# FabDisPendant.net
KiCad netlist of a schematic drawn in EAGLE
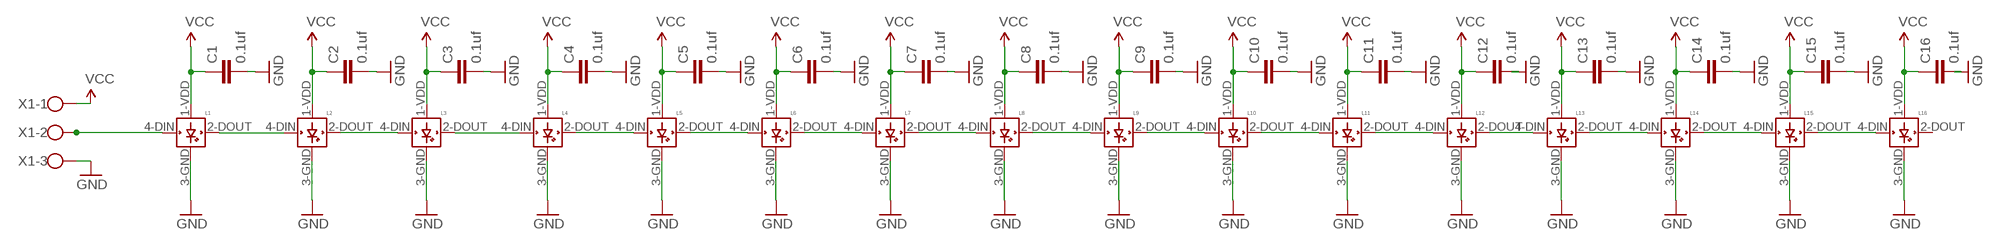
[diagram p0: schematic, sheet 1]

(export (version "E")
  (design (tool "Eeschema 10.0.6"))
  (components
    (comp (ref "C1")
      (value "0.1uf")
      (footprint "eagle-import:0603-CAP")
      (libsource (lib "eagle-import") (part "CAP0603-CAP"))
    )
    (comp (ref "C2")
      (value "0.1uf")
      (footprint "eagle-import:0603-CAP")
      (libsource (lib "eagle-import") (part "CAP0603-CAP"))
    )
    (comp (ref "C3")
      (value "0.1uf")
      (footprint "eagle-import:0603-CAP")
      (libsource (lib "eagle-import") (part "CAP0603-CAP"))
    )
    (comp (ref "C4")
      (value "0.1uf")
      (footprint "eagle-import:0603-CAP")
      (libsource (lib "eagle-import") (part "CAP0603-CAP"))
    )
    (comp (ref "C5")
      (value "0.1uf")
      (footprint "eagle-import:0603-CAP")
      (libsource (lib "eagle-import") (part "CAP0603-CAP"))
    )
    (comp (ref "C6")
      (value "0.1uf")
      (footprint "eagle-import:0603-CAP")
      (libsource (lib "eagle-import") (part "CAP0603-CAP"))
    )
    (comp (ref "C7")
      (value "0.1uf")
      (footprint "eagle-import:0603-CAP")
      (libsource (lib "eagle-import") (part "CAP0603-CAP"))
    )
    (comp (ref "C8")
      (value "0.1uf")
      (footprint "eagle-import:0603-CAP")
      (libsource (lib "eagle-import") (part "CAP0603-CAP"))
    )
    (comp (ref "C9")
      (value "0.1uf")
      (footprint "eagle-import:0603-CAP")
      (libsource (lib "eagle-import") (part "CAP0603-CAP"))
    )
    (comp (ref "C10")
      (value "0.1uf")
      (footprint "eagle-import:0603-CAP")
      (libsource (lib "eagle-import") (part "CAP0603-CAP"))
    )
    (comp (ref "C11")
      (value "0.1uf")
      (footprint "eagle-import:0603-CAP")
      (libsource (lib "eagle-import") (part "CAP0603-CAP"))
    )
    (comp (ref "C12")
      (value "0.1uf")
      (footprint "eagle-import:0603-CAP")
      (libsource (lib "eagle-import") (part "CAP0603-CAP"))
    )
    (comp (ref "C13")
      (value "0.1uf")
      (footprint "eagle-import:0603-CAP")
      (libsource (lib "eagle-import") (part "CAP0603-CAP"))
    )
    (comp (ref "C14")
      (value "0.1uf")
      (footprint "eagle-import:0603-CAP")
      (libsource (lib "eagle-import") (part "CAP0603-CAP"))
    )
    (comp (ref "C15")
      (value "0.1uf")
      (footprint "eagle-import:0603-CAP")
      (libsource (lib "eagle-import") (part "CAP0603-CAP"))
    )
    (comp (ref "C16")
      (value "0.1uf")
      (footprint "eagle-import:0603-CAP")
      (libsource (lib "eagle-import") (part "CAP0603-CAP"))
    )
    (comp (ref "L1")
      (value "WS2812B")
      (footprint "eagle-import:WS2812B")
      (libsource (lib "eagle-import") (part "WS2812B"))
    )
    (comp (ref "L2")
      (value "WS2812B")
      (footprint "eagle-import:WS2812B")
      (libsource (lib "eagle-import") (part "WS2812B"))
    )
    (comp (ref "L3")
      (value "WS2812B")
      (footprint "eagle-import:WS2812B")
      (libsource (lib "eagle-import") (part "WS2812B"))
    )
    (comp (ref "L4")
      (value "WS2812B")
      (footprint "eagle-import:WS2812B")
      (libsource (lib "eagle-import") (part "WS2812B"))
    )
    (comp (ref "L5")
      (value "WS2812B")
      (footprint "eagle-import:WS2812B")
      (libsource (lib "eagle-import") (part "WS2812B"))
    )
    (comp (ref "L6")
      (value "WS2812B")
      (footprint "eagle-import:WS2812B")
      (libsource (lib "eagle-import") (part "WS2812B"))
    )
    (comp (ref "L7")
      (value "WS2812B")
      (footprint "eagle-import:WS2812B")
      (libsource (lib "eagle-import") (part "WS2812B"))
    )
    (comp (ref "L8")
      (value "WS2812B")
      (footprint "eagle-import:WS2812B")
      (libsource (lib "eagle-import") (part "WS2812B"))
    )
    (comp (ref "L9")
      (value "WS2812B")
      (footprint "eagle-import:WS2812B")
      (libsource (lib "eagle-import") (part "WS2812B"))
    )
    (comp (ref "L10")
      (value "WS2812B")
      (footprint "eagle-import:WS2812B")
      (libsource (lib "eagle-import") (part "WS2812B"))
    )
    (comp (ref "L11")
      (value "WS2812B")
      (footprint "eagle-import:WS2812B")
      (libsource (lib "eagle-import") (part "WS2812B"))
    )
    (comp (ref "L12")
      (value "WS2812B")
      (footprint "eagle-import:WS2812B")
      (libsource (lib "eagle-import") (part "WS2812B"))
    )
    (comp (ref "L13")
      (value "WS2812B")
      (footprint "eagle-import:WS2812B")
      (libsource (lib "eagle-import") (part "WS2812B"))
    )
    (comp (ref "L14")
      (value "WS2812B")
      (footprint "eagle-import:WS2812B")
      (libsource (lib "eagle-import") (part "WS2812B"))
    )
    (comp (ref "L15")
      (value "WS2812B")
      (footprint "eagle-import:WS2812B")
      (libsource (lib "eagle-import") (part "WS2812B"))
    )
    (comp (ref "L16")
      (value "WS2812B")
      (footprint "eagle-import:WS2812B")
      (libsource (lib "eagle-import") (part "WS2812B"))
    )
    (comp (ref "X1")
      (value "W237-103")
      (footprint "eagle-import:W237-103")
      (fields (field (name "MPN") "237-103"))
      (libsource (lib "eagle-import") (part "W237-103"))
    )
  )
  (nets
    (net (code "1") (name "GND") (class "Default")
      (node (ref "C1") (pin "2") (pinfunction "2_2") (pintype "passive"))
      (node (ref "C10") (pin "2") (pinfunction "2_2") (pintype "passive"))
      (node (ref "C11") (pin "2") (pinfunction "2_2") (pintype "passive"))
      (node (ref "C12") (pin "2") (pinfunction "2_2") (pintype "passive"))
      (node (ref "C13") (pin "2") (pinfunction "2_2") (pintype "passive"))
      (node (ref "C14") (pin "2") (pinfunction "2_2") (pintype "passive"))
      (node (ref "C15") (pin "2") (pinfunction "2_2") (pintype "passive"))
      (node (ref "C16") (pin "2") (pinfunction "2_2") (pintype "passive"))
      (node (ref "C2") (pin "2") (pinfunction "2_2") (pintype "passive"))
      (node (ref "C3") (pin "2") (pinfunction "2_2") (pintype "passive"))
      (node (ref "C4") (pin "2") (pinfunction "2_2") (pintype "passive"))
      (node (ref "C5") (pin "2") (pinfunction "2_2") (pintype "passive"))
      (node (ref "C6") (pin "2") (pinfunction "2_2") (pintype "passive"))
      (node (ref "C7") (pin "2") (pinfunction "2_2") (pintype "passive"))
      (node (ref "C8") (pin "2") (pinfunction "2_2") (pintype "passive"))
      (node (ref "C9") (pin "2") (pinfunction "2_2") (pintype "passive"))
      (node (ref "L1") (pin "3-GND") (pinfunction "GND_3-GND") (pintype "bidirectional"))
      (node (ref "L10") (pin "3-GND") (pinfunction "GND_3-GND") (pintype "bidirectional"))
      (node (ref "L11") (pin "3-GND") (pinfunction "GND_3-GND") (pintype "bidirectional"))
      (node (ref "L12") (pin "3-GND") (pinfunction "GND_3-GND") (pintype "bidirectional"))
      (node (ref "L13") (pin "3-GND") (pinfunction "GND_3-GND") (pintype "bidirectional"))
      (node (ref "L14") (pin "3-GND") (pinfunction "GND_3-GND") (pintype "bidirectional"))
      (node (ref "L15") (pin "3-GND") (pinfunction "GND_3-GND") (pintype "bidirectional"))
      (node (ref "L16") (pin "3-GND") (pinfunction "GND_3-GND") (pintype "bidirectional"))
      (node (ref "L2") (pin "3-GND") (pinfunction "GND_3-GND") (pintype "bidirectional"))
      (node (ref "L3") (pin "3-GND") (pinfunction "GND_3-GND") (pintype "bidirectional"))
      (node (ref "L4") (pin "3-GND") (pinfunction "GND_3-GND") (pintype "bidirectional"))
      (node (ref "L5") (pin "3-GND") (pinfunction "GND_3-GND") (pintype "bidirectional"))
      (node (ref "L6") (pin "3-GND") (pinfunction "GND_3-GND") (pintype "bidirectional"))
      (node (ref "L7") (pin "3-GND") (pinfunction "GND_3-GND") (pintype "bidirectional"))
      (node (ref "L8") (pin "3-GND") (pinfunction "GND_3-GND") (pintype "bidirectional"))
      (node (ref "L9") (pin "3-GND") (pinfunction "GND_3-GND") (pintype "bidirectional"))
      (node (ref "X1") (pin "3") (pinfunction "KL_3") (pintype "passive"))
    )
    (net (code "2") (name "Net-(L1-DIN)") (class "Default")
      (node (ref "L1") (pin "4-DIN") (pinfunction "DIN_4-DIN") (pintype "input"))
      (node (ref "X1") (pin "2") (pinfunction "KL_2") (pintype "passive"))
    )
    (net (code "3") (name "Net-(L1-DOUT)") (class "Default")
      (node (ref "L1") (pin "2-DOUT") (pinfunction "DOUT_2-DOUT") (pintype "output"))
      (node (ref "L2") (pin "4-DIN") (pinfunction "DIN_4-DIN") (pintype "input"))
    )
    (net (code "4") (name "Net-(L2-DOUT)") (class "Default")
      (node (ref "L2") (pin "2-DOUT") (pinfunction "DOUT_2-DOUT") (pintype "output"))
      (node (ref "L3") (pin "4-DIN") (pinfunction "DIN_4-DIN") (pintype "input"))
    )
    (net (code "5") (name "Net-(L3-DOUT)") (class "Default")
      (node (ref "L3") (pin "2-DOUT") (pinfunction "DOUT_2-DOUT") (pintype "output"))
      (node (ref "L4") (pin "4-DIN") (pinfunction "DIN_4-DIN") (pintype "input"))
    )
    (net (code "6") (name "Net-(L4-DOUT)") (class "Default")
      (node (ref "L4") (pin "2-DOUT") (pinfunction "DOUT_2-DOUT") (pintype "output"))
      (node (ref "L5") (pin "4-DIN") (pinfunction "DIN_4-DIN") (pintype "input"))
    )
    (net (code "7") (name "Net-(L5-DOUT)") (class "Default")
      (node (ref "L5") (pin "2-DOUT") (pinfunction "DOUT_2-DOUT") (pintype "output"))
      (node (ref "L6") (pin "4-DIN") (pinfunction "DIN_4-DIN") (pintype "input"))
    )
    (net (code "8") (name "Net-(L6-DOUT)") (class "Default")
      (node (ref "L6") (pin "2-DOUT") (pinfunction "DOUT_2-DOUT") (pintype "output"))
      (node (ref "L7") (pin "4-DIN") (pinfunction "DIN_4-DIN") (pintype "input"))
    )
    (net (code "9") (name "Net-(L7-DOUT)") (class "Default")
      (node (ref "L7") (pin "2-DOUT") (pinfunction "DOUT_2-DOUT") (pintype "output"))
      (node (ref "L8") (pin "4-DIN") (pinfunction "DIN_4-DIN") (pintype "input"))
    )
    (net (code "10") (name "Net-(L8-DOUT)") (class "Default")
      (node (ref "L8") (pin "2-DOUT") (pinfunction "DOUT_2-DOUT") (pintype "output"))
      (node (ref "L9") (pin "4-DIN") (pinfunction "DIN_4-DIN") (pintype "input"))
    )
    (net (code "11") (name "Net-(L10-DIN)") (class "Default")
      (node (ref "L10") (pin "4-DIN") (pinfunction "DIN_4-DIN") (pintype "input"))
      (node (ref "L9") (pin "2-DOUT") (pinfunction "DOUT_2-DOUT") (pintype "output"))
    )
    (net (code "12") (name "Net-(L10-DOUT)") (class "Default")
      (node (ref "L10") (pin "2-DOUT") (pinfunction "DOUT_2-DOUT") (pintype "output"))
      (node (ref "L11") (pin "4-DIN") (pinfunction "DIN_4-DIN") (pintype "input"))
    )
    (net (code "13") (name "Net-(L11-DOUT)") (class "Default")
      (node (ref "L11") (pin "2-DOUT") (pinfunction "DOUT_2-DOUT") (pintype "output"))
      (node (ref "L12") (pin "4-DIN") (pinfunction "DIN_4-DIN") (pintype "input"))
    )
    (net (code "14") (name "Net-(L12-DOUT)") (class "Default")
      (node (ref "L12") (pin "2-DOUT") (pinfunction "DOUT_2-DOUT") (pintype "output"))
      (node (ref "L13") (pin "4-DIN") (pinfunction "DIN_4-DIN") (pintype "input"))
    )
    (net (code "15") (name "Net-(L13-DOUT)") (class "Default")
      (node (ref "L13") (pin "2-DOUT") (pinfunction "DOUT_2-DOUT") (pintype "output"))
      (node (ref "L14") (pin "4-DIN") (pinfunction "DIN_4-DIN") (pintype "input"))
    )
    (net (code "16") (name "Net-(L14-DOUT)") (class "Default")
      (node (ref "L14") (pin "2-DOUT") (pinfunction "DOUT_2-DOUT") (pintype "output"))
      (node (ref "L15") (pin "4-DIN") (pinfunction "DIN_4-DIN") (pintype "input"))
    )
    (net (code "17") (name "Net-(L15-DOUT)") (class "Default")
      (node (ref "L15") (pin "2-DOUT") (pinfunction "DOUT_2-DOUT") (pintype "output"))
      (node (ref "L16") (pin "4-DIN") (pinfunction "DIN_4-DIN") (pintype "input"))
    )
    (net (code "18") (name "VCC") (class "Default")
      (node (ref "C1") (pin "1") (pinfunction "1_1") (pintype "passive"))
      (node (ref "C10") (pin "1") (pinfunction "1_1") (pintype "passive"))
      (node (ref "C11") (pin "1") (pinfunction "1_1") (pintype "passive"))
      (node (ref "C12") (pin "1") (pinfunction "1_1") (pintype "passive"))
      (node (ref "C13") (pin "1") (pinfunction "1_1") (pintype "passive"))
      (node (ref "C14") (pin "1") (pinfunction "1_1") (pintype "passive"))
      (node (ref "C15") (pin "1") (pinfunction "1_1") (pintype "passive"))
      (node (ref "C16") (pin "1") (pinfunction "1_1") (pintype "passive"))
      (node (ref "C2") (pin "1") (pinfunction "1_1") (pintype "passive"))
      (node (ref "C3") (pin "1") (pinfunction "1_1") (pintype "passive"))
      (node (ref "C4") (pin "1") (pinfunction "1_1") (pintype "passive"))
      (node (ref "C5") (pin "1") (pinfunction "1_1") (pintype "passive"))
      (node (ref "C6") (pin "1") (pinfunction "1_1") (pintype "passive"))
      (node (ref "C7") (pin "1") (pinfunction "1_1") (pintype "passive"))
      (node (ref "C8") (pin "1") (pinfunction "1_1") (pintype "passive"))
      (node (ref "C9") (pin "1") (pinfunction "1_1") (pintype "passive"))
      (node (ref "L1") (pin "1-VDD") (pinfunction "VDD_1-VDD") (pintype "bidirectional"))
      (node (ref "L10") (pin "1-VDD") (pinfunction "VDD_1-VDD") (pintype "bidirectional"))
      (node (ref "L11") (pin "1-VDD") (pinfunction "VDD_1-VDD") (pintype "bidirectional"))
      (node (ref "L12") (pin "1-VDD") (pinfunction "VDD_1-VDD") (pintype "bidirectional"))
      (node (ref "L13") (pin "1-VDD") (pinfunction "VDD_1-VDD") (pintype "bidirectional"))
      (node (ref "L14") (pin "1-VDD") (pinfunction "VDD_1-VDD") (pintype "bidirectional"))
      (node (ref "L15") (pin "1-VDD") (pinfunction "VDD_1-VDD") (pintype "bidirectional"))
      (node (ref "L16") (pin "1-VDD") (pinfunction "VDD_1-VDD") (pintype "bidirectional"))
      (node (ref "L2") (pin "1-VDD") (pinfunction "VDD_1-VDD") (pintype "bidirectional"))
      (node (ref "L3") (pin "1-VDD") (pinfunction "VDD_1-VDD") (pintype "bidirectional"))
      (node (ref "L4") (pin "1-VDD") (pinfunction "VDD_1-VDD") (pintype "bidirectional"))
      (node (ref "L5") (pin "1-VDD") (pinfunction "VDD_1-VDD") (pintype "bidirectional"))
      (node (ref "L6") (pin "1-VDD") (pinfunction "VDD_1-VDD") (pintype "bidirectional"))
      (node (ref "L7") (pin "1-VDD") (pinfunction "VDD_1-VDD") (pintype "bidirectional"))
      (node (ref "L8") (pin "1-VDD") (pinfunction "VDD_1-VDD") (pintype "bidirectional"))
      (node (ref "L9") (pin "1-VDD") (pinfunction "VDD_1-VDD") (pintype "bidirectional"))
      (node (ref "X1") (pin "1") (pinfunction "KL_1") (pintype "passive"))
    )
    (net (code "19") (name "unconnected-(L16-DOUT-Pad2-DOUT)") (class "Default")
      (node (ref "L16") (pin "2-DOUT") (pinfunction "DOUT_2-DOUT") (pintype "output"))
    )
  )
)
